# small_Eagle_1.net
KiCad netlist of a schematic drawn in EAGLE
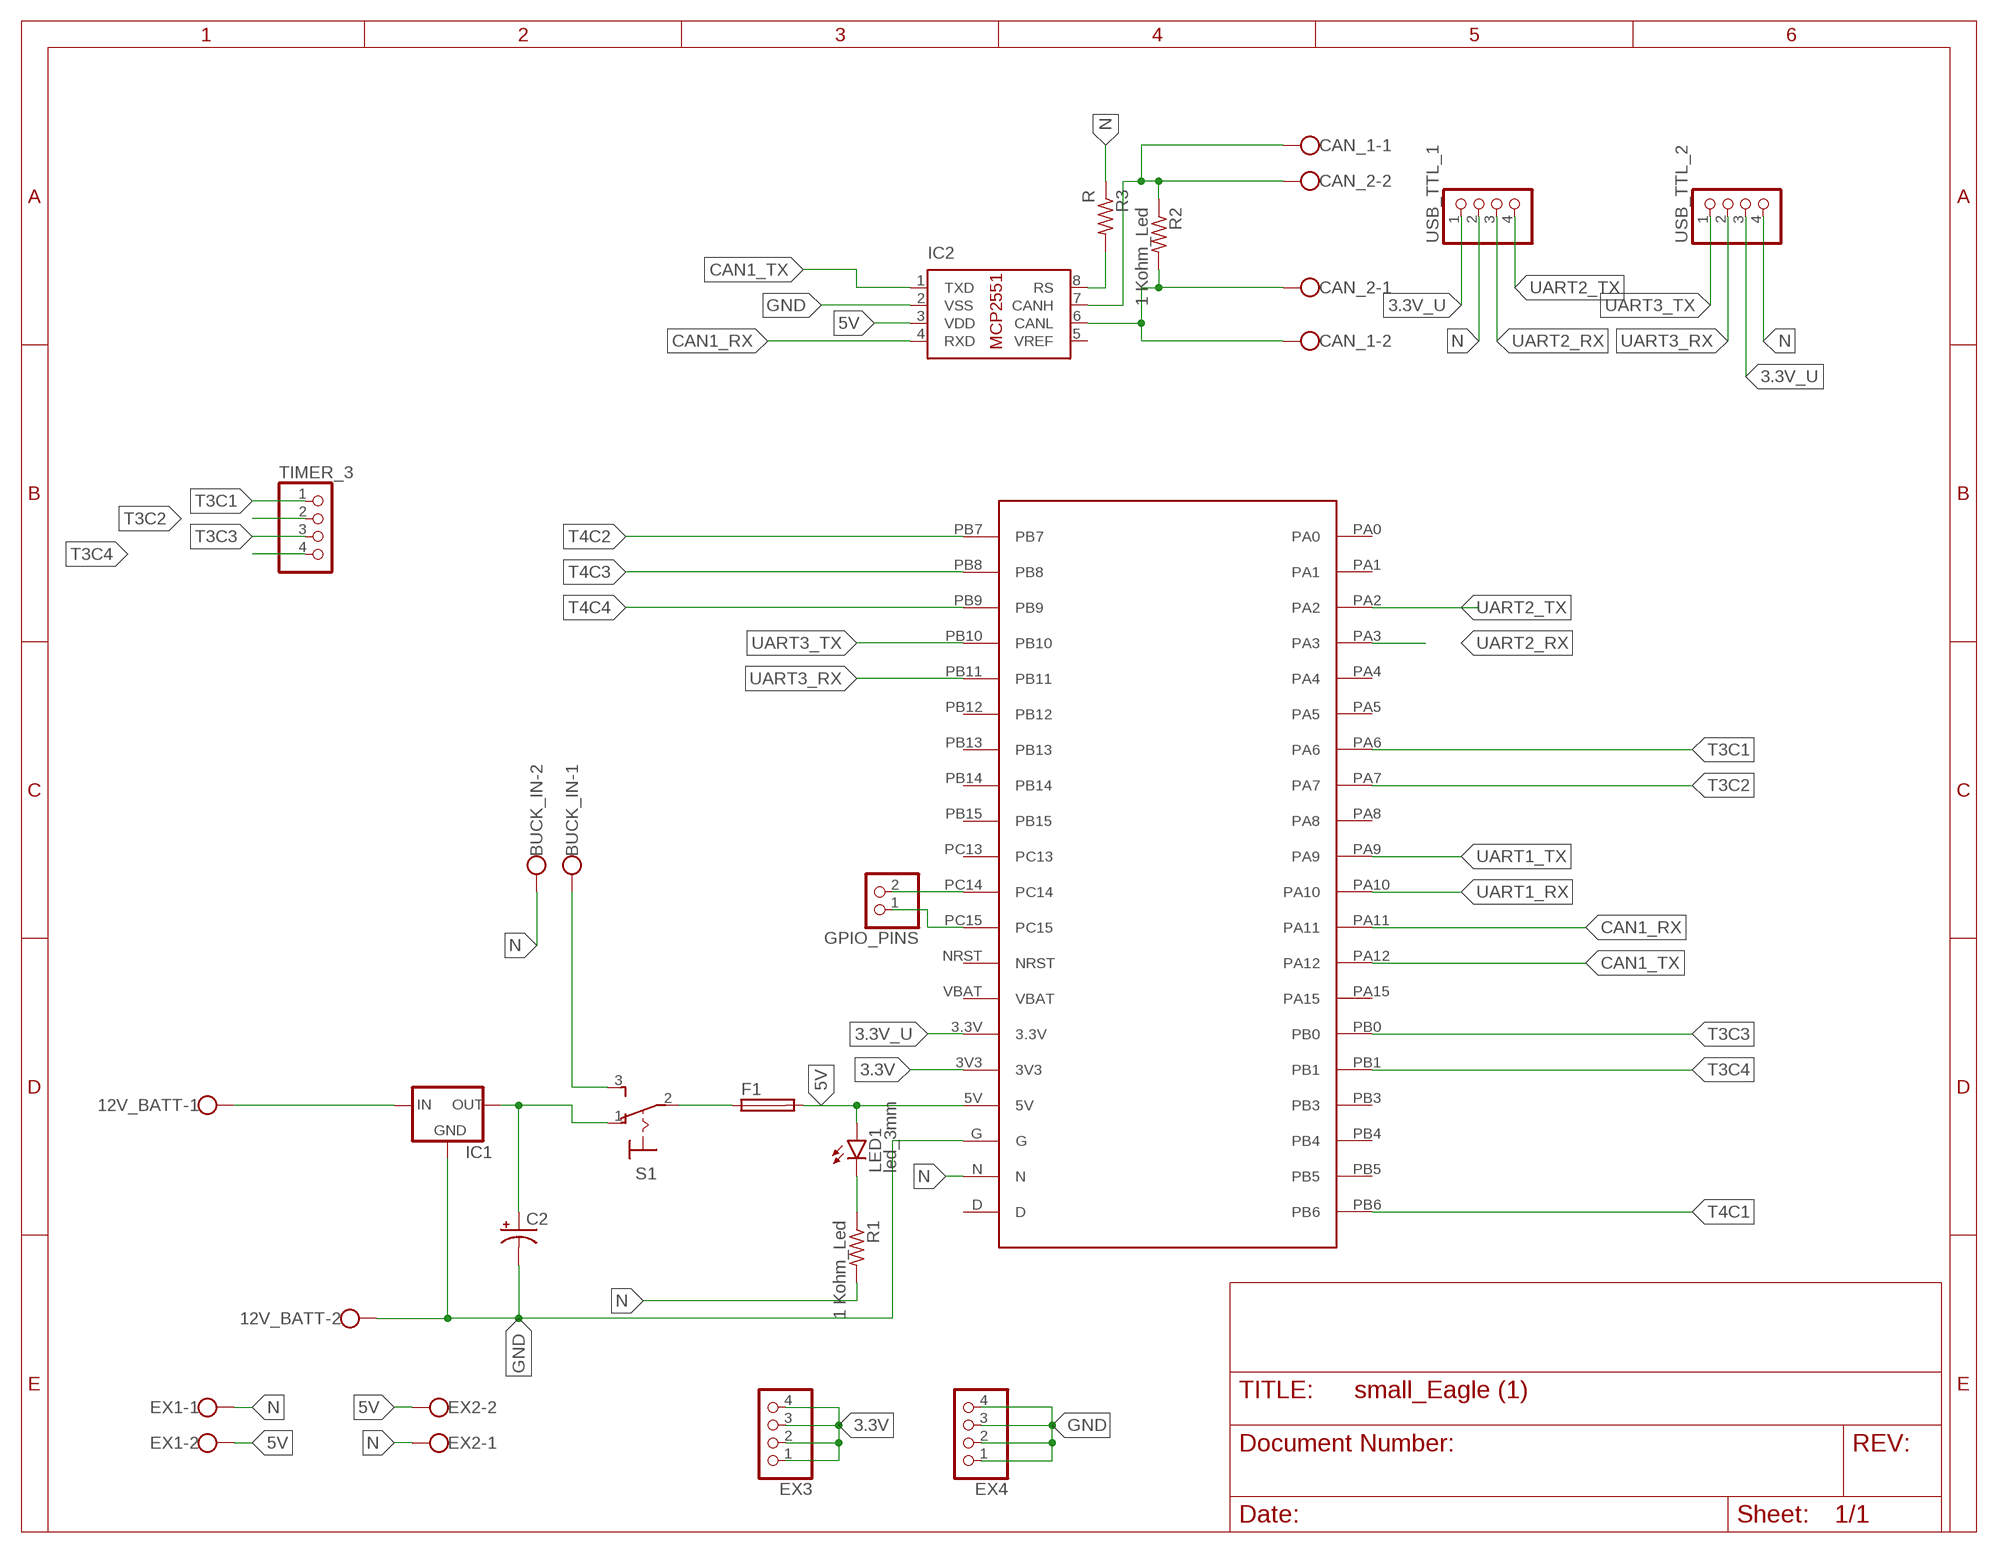
[diagram p0: schematic, sheet 1]

(export (version "E")
  (design (tool "Eeschema 10.0.6"))
  (components
    (comp (ref "12V_BATT")
      (value "W237-102")
      (footprint "eagle-import:W237-102")
      (fields (field (name "MPN") "237-102"))
      (libsource (lib "eagle-import") (part "W237-102"))
    )
    (comp (ref "BUCK_IN")
      (value "W237-102")
      (footprint "eagle-import:W237-102")
      (fields (field (name "MPN") "237-102"))
      (libsource (lib "eagle-import") (part "W237-102"))
    )
    (comp (ref "C2")
      (value "CPOL-USE2-4")
      (footprint "eagle-import:E2-4")
      (libsource (lib "eagle-import") (part "CPOL-USE2-4"))
    )
    (comp (ref "CAN_1")
      (value "W237-102")
      (footprint "eagle-import:W237-102")
      (fields (field (name "MPN") "237-102"))
      (libsource (lib "eagle-import") (part "W237-102"))
    )
    (comp (ref "CAN_2")
      (value "W237-102")
      (footprint "eagle-import:W237-102")
      (fields (field (name "MPN") "237-102"))
      (libsource (lib "eagle-import") (part "W237-102"))
    )
    (comp (ref "EX1")
      (value "W237-102")
      (footprint "eagle-import:W237-102")
      (fields (field (name "MPN") "237-102"))
      (libsource (lib "eagle-import") (part "W237-102"))
    )
    (comp (ref "EX2")
      (value "W237-102")
      (footprint "eagle-import:W237-102")
      (fields (field (name "MPN") "237-102"))
      (libsource (lib "eagle-import") (part "W237-102"))
    )
    (comp (ref "EX3")
      (value "PINHD-1X4")
      (footprint "eagle-import:1X04")
      (libsource (lib "eagle-import") (part "PINHD-1X4"))
    )
    (comp (ref "EX4")
      (value "PINHD-1X4")
      (footprint "eagle-import:1X04")
      (libsource (lib "eagle-import") (part "PINHD-1X4"))
    )
    (comp (ref "F1")
      (value "GSH15")
      (footprint "eagle-import:GSH15")
      (fields (field (name "MPN") "64900001039"))
      (libsource (lib "eagle-import") (part "GSH15"))
    )
    (comp (ref "GPIO_PINS")
      (value "PINHD-1X2")
      (footprint "eagle-import:1X02")
      (libsource (lib "eagle-import") (part "PINHD-1X2"))
    )
    (comp (ref "IC1")
      (value "78XXS")
      (footprint "eagle-import:78XXS")
      (libsource (lib "eagle-import") (part "78XXS"))
    )
    (comp (ref "IC2")
      (value "MCP2551/P")
      (footprint "eagle-import:DIL08")
      (libsource (lib "eagle-import") (part "MCP2551/P"))
    )
    (comp (ref "LED1")
      (value "led_3mm")
      (footprint "eagle-import:LED3MM")
      (libsource (lib "eagle-import") (part "LED3MM"))
    )
    (comp (ref "R1")
      (value "1 Kohm_Led")
      (footprint "eagle-import:0207_7")
      (libsource (lib "eagle-import") (part "R-US_0207/7"))
    )
    (comp (ref "R2")
      (value "1 Kohm_Led")
      (footprint "eagle-import:0207_7")
      (libsource (lib "eagle-import") (part "R-US_0207/7"))
    )
    (comp (ref "R3")
      (value "R")
      (footprint "eagle-import:0207_7")
      (libsource (lib "eagle-import") (part "R-US_0207/7"))
    )
    (comp (ref "S1")
      (value "320-916")
      (footprint "eagle-import:320-916")
      (libsource (lib "eagle-import") (part "320-916"))
    )
    (comp (ref "TIMER_3")
      (value "PINHD-1X4")
      (footprint "eagle-import:1X04")
      (libsource (lib "eagle-import") (part "PINHD-1X4"))
    )
    (comp (ref "U$1")
      (value "STM32F103C8")
      (footprint "eagle-import:DIP")
      (libsource (lib "eagle-import") (part "STM32F103C8"))
    )
    (comp (ref "USB_TTL_1")
      (value "PINHD-1X4")
      (footprint "eagle-import:1X04")
      (libsource (lib "eagle-import") (part "PINHD-1X4"))
    )
    (comp (ref "USB_TTL_2")
      (value "PINHD-1X4")
      (footprint "eagle-import:1X04")
      (libsource (lib "eagle-import") (part "PINHD-1X4"))
    )
  )
  (nets
    (net (code "1") (name "3.3V") (class "Default")
      (node (ref "EX3") (pin "1") (pinfunction "1_1") (pintype "passive"))
      (node (ref "EX3") (pin "2") (pinfunction "2_2") (pintype "passive"))
      (node (ref "EX3") (pin "3") (pinfunction "3_3") (pintype "passive"))
      (node (ref "EX3") (pin "4") (pinfunction "4_4") (pintype "passive"))
      (node (ref "U$1") (pin "3V3") (pinfunction "3V3_3V3") (pintype "bidirectional"))
    )
    (net (code "2") (name "3.3V_U") (class "Default")
      (node (ref "U$1") (pin "3.3V") (pinfunction "3.3V_3.3V") (pintype "bidirectional"))
      (node (ref "USB_TTL_1") (pin "1") (pinfunction "1_1") (pintype "passive"))
      (node (ref "USB_TTL_2") (pin "3") (pinfunction "3_3") (pintype "passive"))
    )
    (net (code "3") (name "5V") (class "Default")
      (node (ref "EX1") (pin "2") (pinfunction "KL_2") (pintype "passive"))
      (node (ref "EX2") (pin "2") (pinfunction "KL_2") (pintype "passive"))
      (node (ref "F1") (pin "2") (pinfunction "2_2") (pintype "passive"))
      (node (ref "IC2") (pin "3") (pinfunction "VDD_3") (pintype "power_in"))
      (node (ref "LED1") (pin "A") (pinfunction "A_A") (pintype "passive"))
      (node (ref "U$1") (pin "5V") (pinfunction "5V_5V") (pintype "bidirectional"))
    )
    (net (code "4") (name "CAN1_RX") (class "Default")
      (node (ref "IC2") (pin "4") (pinfunction "RXD_4") (pintype "output"))
      (node (ref "U$1") (pin "PA11") (pinfunction "PA11_PA11") (pintype "bidirectional"))
    )
    (net (code "5") (name "CAN1_TX") (class "Default")
      (node (ref "IC2") (pin "1") (pinfunction "TXD_1") (pintype "input"))
      (node (ref "U$1") (pin "PA12") (pinfunction "PA12_PA12") (pintype "bidirectional"))
    )
    (net (code "6") (name "GND") (class "Default")
      (node (ref "12V_BATT") (pin "2") (pinfunction "KL_2") (pintype "passive"))
      (node (ref "C2") (pin "-") (pinfunction "-_-") (pintype "passive"))
      (node (ref "EX4") (pin "1") (pinfunction "1_1") (pintype "passive"))
      (node (ref "EX4") (pin "2") (pinfunction "2_2") (pintype "passive"))
      (node (ref "EX4") (pin "3") (pinfunction "3_3") (pintype "passive"))
      (node (ref "EX4") (pin "4") (pinfunction "4_4") (pintype "passive"))
      (node (ref "IC1") (pin "GND") (pinfunction "GND_GND") (pintype "input"))
      (node (ref "IC2") (pin "2") (pinfunction "VSS_2") (pintype "power_in"))
      (node (ref "U$1") (pin "G") (pinfunction "G_G") (pintype "bidirectional"))
    )
    (net (code "7") (name "N") (class "Default")
      (node (ref "BUCK_IN") (pin "2") (pinfunction "KL_2") (pintype "passive"))
      (node (ref "EX1") (pin "1") (pinfunction "KL_1") (pintype "passive"))
      (node (ref "EX2") (pin "1") (pinfunction "KL_1") (pintype "passive"))
      (node (ref "R1") (pin "2") (pinfunction "2_2") (pintype "passive"))
      (node (ref "R3") (pin "1") (pinfunction "1_1") (pintype "passive"))
      (node (ref "U$1") (pin "N") (pinfunction "N_N") (pintype "bidirectional"))
      (node (ref "USB_TTL_1") (pin "2") (pinfunction "2_2") (pintype "passive"))
      (node (ref "USB_TTL_2") (pin "4") (pinfunction "4_4") (pintype "passive"))
    )
    (net (code "8") (name "Net-(12V_BATTA-KL)") (class "Default")
      (node (ref "12V_BATT") (pin "1") (pinfunction "KL_1") (pintype "passive"))
      (node (ref "IC1") (pin "IN") (pinfunction "IN_IN") (pintype "input"))
    )
    (net (code "9") (name "Net-(BUCK_INA-KL)") (class "Default")
      (node (ref "BUCK_IN") (pin "1") (pinfunction "KL_1") (pintype "passive"))
      (node (ref "S1") (pin "3") (pinfunction "S_3") (pintype "passive"))
    )
    (net (code "10") (name "Net-(CAN_1A-KL)") (class "Default")
      (node (ref "CAN_1") (pin "1") (pinfunction "KL_1") (pintype "passive"))
      (node (ref "CAN_2") (pin "2") (pinfunction "KL_2") (pintype "passive"))
      (node (ref "IC2") (pin "7") (pinfunction "CANH_7") (pintype "bidirectional"))
      (node (ref "R2") (pin "1") (pinfunction "1_1") (pintype "passive"))
    )
    (net (code "11") (name "Net-(CAN_1B-KL)") (class "Default")
      (node (ref "CAN_1") (pin "2") (pinfunction "KL_2") (pintype "passive"))
      (node (ref "CAN_2") (pin "1") (pinfunction "KL_1") (pintype "passive"))
      (node (ref "IC2") (pin "6") (pinfunction "CANL_6") (pintype "bidirectional"))
      (node (ref "R2") (pin "2") (pinfunction "2_2") (pintype "passive"))
    )
    (net (code "12") (name "Net-(GPIO_PINS-Pad1)") (class "Default")
      (node (ref "GPIO_PINS") (pin "1") (pinfunction "1_1") (pintype "passive"))
      (node (ref "U$1") (pin "PC15") (pinfunction "PC15_PC15") (pintype "bidirectional"))
    )
    (net (code "13") (name "Net-(GPIO_PINS-Pad2)") (class "Default")
      (node (ref "GPIO_PINS") (pin "2") (pinfunction "2_2") (pintype "passive"))
      (node (ref "U$1") (pin "PC14") (pinfunction "PC14_PC14") (pintype "bidirectional"))
    )
    (net (code "14") (name "Net-(IC2-RS)") (class "Default")
      (node (ref "IC2") (pin "8") (pinfunction "RS_8") (pintype "input"))
      (node (ref "R3") (pin "2") (pinfunction "2_2") (pintype "passive"))
    )
    (net (code "15") (name "Net-(LED1-C)") (class "Default")
      (node (ref "LED1") (pin "K") (pinfunction "C_K") (pintype "passive"))
      (node (ref "R1") (pin "1") (pinfunction "1_1") (pintype "passive"))
    )
    (net (code "16") (name "Net-(S1-O)") (class "Default")
      (node (ref "C2") (pin "+") (pinfunction "+_+") (pintype "passive"))
      (node (ref "IC1") (pin "OUT") (pinfunction "OUT_OUT") (pintype "passive"))
      (node (ref "S1") (pin "1") (pinfunction "O_1") (pintype "passive"))
    )
    (net (code "17") (name "Net-(S1-P)") (class "Default")
      (node (ref "F1") (pin "1") (pinfunction "1_1") (pintype "passive"))
      (node (ref "S1") (pin "2") (pinfunction "P_2") (pintype "passive"))
    )
    (net (code "18") (name "T3C1") (class "Default")
      (node (ref "TIMER_3") (pin "1") (pinfunction "1_1") (pintype "passive"))
      (node (ref "U$1") (pin "PA6") (pinfunction "PA6_PA6") (pintype "bidirectional"))
    )
    (net (code "19") (name "T3C2") (class "Default")
      (node (ref "TIMER_3") (pin "2") (pinfunction "2_2") (pintype "passive"))
      (node (ref "U$1") (pin "PA7") (pinfunction "PA7_PA7") (pintype "bidirectional"))
    )
    (net (code "20") (name "T3C3") (class "Default")
      (node (ref "TIMER_3") (pin "3") (pinfunction "3_3") (pintype "passive"))
      (node (ref "U$1") (pin "PB0") (pinfunction "PB0_PB0") (pintype "bidirectional"))
    )
    (net (code "21") (name "T3C4") (class "Default")
      (node (ref "TIMER_3") (pin "4") (pinfunction "4_4") (pintype "passive"))
      (node (ref "U$1") (pin "PB1") (pinfunction "PB1_PB1") (pintype "bidirectional"))
    )
    (net (code "22") (name "T4C1") (class "Default")
      (node (ref "U$1") (pin "PB6") (pinfunction "PB6_PB6") (pintype "bidirectional"))
    )
    (net (code "23") (name "T4C2") (class "Default")
      (node (ref "U$1") (pin "PB7") (pinfunction "PB7_PB7") (pintype "bidirectional"))
    )
    (net (code "24") (name "T4C3") (class "Default")
      (node (ref "U$1") (pin "PB8") (pinfunction "PB8_PB8") (pintype "bidirectional"))
    )
    (net (code "25") (name "T4C4") (class "Default")
      (node (ref "U$1") (pin "PB9") (pinfunction "PB9_PB9") (pintype "bidirectional"))
    )
    (net (code "26") (name "UART1_RX") (class "Default")
      (node (ref "U$1") (pin "PA10") (pinfunction "PA10_PA10") (pintype "bidirectional"))
    )
    (net (code "27") (name "UART1_TX") (class "Default")
      (node (ref "U$1") (pin "PA9") (pinfunction "PA9_PA9") (pintype "bidirectional"))
    )
    (net (code "28") (name "UART2_RX") (class "Default")
      (node (ref "U$1") (pin "PA3") (pinfunction "PA3_PA3") (pintype "bidirectional"))
      (node (ref "USB_TTL_1") (pin "3") (pinfunction "3_3") (pintype "passive"))
    )
    (net (code "29") (name "UART2_TX") (class "Default")
      (node (ref "U$1") (pin "PA2") (pinfunction "PA2_PA2") (pintype "bidirectional"))
      (node (ref "USB_TTL_1") (pin "4") (pinfunction "4_4") (pintype "passive"))
    )
    (net (code "30") (name "UART3_RX") (class "Default")
      (node (ref "U$1") (pin "PB11") (pinfunction "PB11_PB11") (pintype "bidirectional"))
      (node (ref "USB_TTL_2") (pin "2") (pinfunction "2_2") (pintype "passive"))
    )
    (net (code "31") (name "UART3_TX") (class "Default")
      (node (ref "U$1") (pin "PB10") (pinfunction "PB10_PB10") (pintype "bidirectional"))
      (node (ref "USB_TTL_2") (pin "1") (pinfunction "1_1") (pintype "passive"))
    )
    (net (code "32") (name "unconnected-(IC2-VREF-Pad5)") (class "Default")
      (node (ref "IC2") (pin "5") (pinfunction "VREF_5") (pintype "output"))
    )
    (net (code "33") (name "unconnected-(U$1-PadD)") (class "Default")
      (node (ref "U$1") (pin "D") (pinfunction "D_D") (pintype "bidirectional"))
    )
    (net (code "34") (name "unconnected-(U$1-PadNRST)") (class "Default")
      (node (ref "U$1") (pin "NRST") (pinfunction "NRST_NRST") (pintype "bidirectional"))
    )
    (net (code "35") (name "unconnected-(U$1-PadPA0)") (class "Default")
      (node (ref "U$1") (pin "PA0") (pinfunction "PA0_PA0") (pintype "bidirectional"))
    )
    (net (code "36") (name "unconnected-(U$1-PadPA1)") (class "Default")
      (node (ref "U$1") (pin "PA1") (pinfunction "PA1_PA1") (pintype "bidirectional"))
    )
    (net (code "37") (name "unconnected-(U$1-PadPA4)") (class "Default")
      (node (ref "U$1") (pin "PA4") (pinfunction "PA4_PA4") (pintype "bidirectional"))
    )
    (net (code "38") (name "unconnected-(U$1-PadPA5)") (class "Default")
      (node (ref "U$1") (pin "PA5") (pinfunction "PA5_PA5") (pintype "bidirectional"))
    )
    (net (code "39") (name "unconnected-(U$1-PadPA8)") (class "Default")
      (node (ref "U$1") (pin "PA8") (pinfunction "PA8_PA8") (pintype "bidirectional"))
    )
    (net (code "40") (name "unconnected-(U$1-PadPA15)") (class "Default")
      (node (ref "U$1") (pin "PA15") (pinfunction "PA15_PA15") (pintype "bidirectional"))
    )
    (net (code "41") (name "unconnected-(U$1-PadPB3)") (class "Default")
      (node (ref "U$1") (pin "PB3") (pinfunction "PB3_PB3") (pintype "bidirectional"))
    )
    (net (code "42") (name "unconnected-(U$1-PadPB4)") (class "Default")
      (node (ref "U$1") (pin "PB4") (pinfunction "PB4_PB4") (pintype "bidirectional"))
    )
    (net (code "43") (name "unconnected-(U$1-PadPB5)") (class "Default")
      (node (ref "U$1") (pin "PB5") (pinfunction "PB5_PB5") (pintype "bidirectional"))
    )
    (net (code "44") (name "unconnected-(U$1-PadPB12)") (class "Default")
      (node (ref "U$1") (pin "PB12") (pinfunction "PB12_PB12") (pintype "bidirectional"))
    )
    (net (code "45") (name "unconnected-(U$1-PadPB13)") (class "Default")
      (node (ref "U$1") (pin "PB13") (pinfunction "PB13_PB13") (pintype "bidirectional"))
    )
    (net (code "46") (name "unconnected-(U$1-PadPB14)") (class "Default")
      (node (ref "U$1") (pin "PB14") (pinfunction "PB14_PB14") (pintype "bidirectional"))
    )
    (net (code "47") (name "unconnected-(U$1-PadPB15)") (class "Default")
      (node (ref "U$1") (pin "PB15") (pinfunction "PB15_PB15") (pintype "bidirectional"))
    )
    (net (code "48") (name "unconnected-(U$1-PadPC13)") (class "Default")
      (node (ref "U$1") (pin "PC13") (pinfunction "PC13_PC13") (pintype "bidirectional"))
    )
    (net (code "49") (name "unconnected-(U$1-PadVBAT)") (class "Default")
      (node (ref "U$1") (pin "VBAT") (pinfunction "VBAT_VBAT") (pintype "bidirectional"))
    )
  )
)
